# LTC6803.net
KiCad netlist of a schematic drawn in Altium Designer
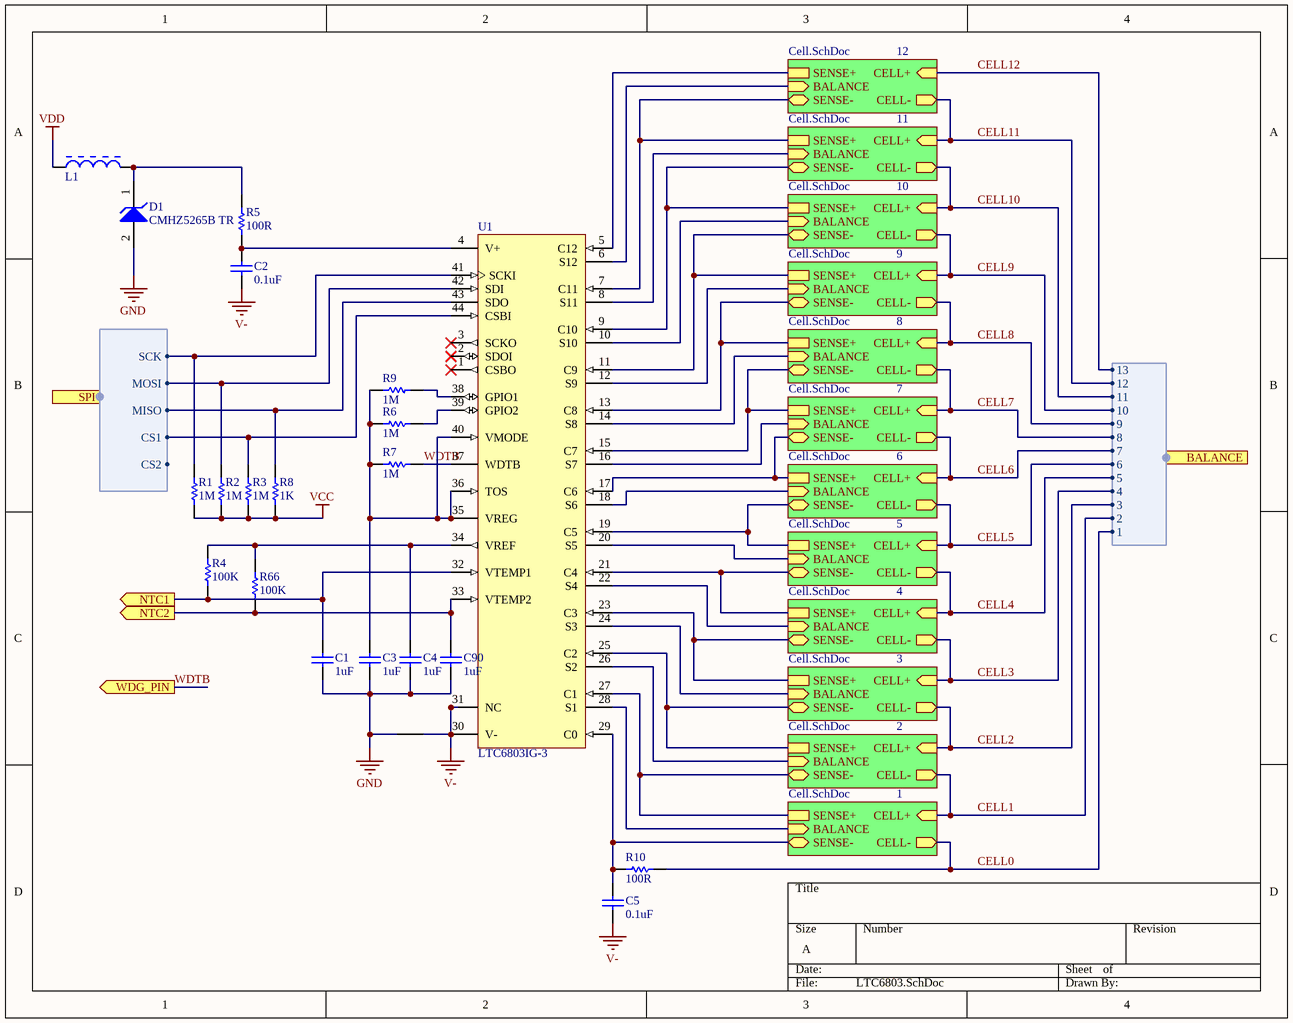
[diagram p0: LTC6803.SchDoc]

(export (version "E")
  (design (tool "Eeschema 10.0.6"))
  (components
    (comp (ref "*") (value "NetTie") (footprint "NetTie") (libsource (lib "Components") (part "NetTie")))
    (comp (ref "C1")
      (value "1uF")
      (footprint "C0603[1608X92]")
      (description "1uF 6.3V 10% 0603 (1608 Metric)")
      (fields (field (name "PARTNUMBER") "GRM188R60J105KA01D") (field (name "MANUFACTURER") "Murata"))
      (libsource (lib "Capacitors") (part "CAP_1uF_6.3V_0603_10%"))
    )
    (comp (ref "C2")
      (value "0.1uF")
      (footprint "C0603[1608X92]")
      (description "0.1uF 100V 10% 0603 (1608 Metric)")
      (fields (field (name "PARTNUMBER") "GRM188R72A104KA35D") (field (name "MANUFACTURER") "Murata"))
      (libsource (lib "Capacitors") (part "CAP_0.1uF_100V_0603_10%"))
    )
    (comp (ref "C3")
      (value "1uF")
      (footprint "C0603[1608X92]")
      (description "1uF 6.3V 10% 0603 (1608 Metric)")
      (fields (field (name "PARTNUMBER") "GRM188R60J105KA01D") (field (name "MANUFACTURER") "Murata"))
      (libsource (lib "Capacitors") (part "CAP_1uF_6.3V_0603_10%"))
    )
    (comp (ref "C4")
      (value "1uF")
      (footprint "C0603[1608X92]")
      (description "1uF 6.3V 10% 0603 (1608 Metric)")
      (fields (field (name "PARTNUMBER") "GRM188R60J105KA01D") (field (name "MANUFACTURER") "Murata"))
      (libsource (lib "Capacitors") (part "CAP_1uF_6.3V_0603_10%"))
    )
    (comp (ref "C5")
      (value "0.1uF")
      (footprint "C0603[1608X92]")
      (description "0.1uF 6.3V 10% 0603 (1608 Metric)")
      (fields (field (name "PARTNUMBER") "GRM188R70J104KA01D") (field (name "MANUFACTURER") "Murata"))
      (libsource (lib "Capacitors") (part "CAP_0.1uF_6.3V_0603_10%"))
    )
    (comp (ref "C90")
      (value "1uF")
      (footprint "C0603[1608X92]")
      (description "1uF 6.3V 10% 0603 (1608 Metric)")
      (fields (field (name "PARTNUMBER") "GRM188R60J105KA01D") (field (name "MANUFACTURER") "Murata"))
      (libsource (lib "Capacitors") (part "CAP_1uF_6.3V_0603_10%"))
    )
    (comp (ref "D1")
      (value "CMHZ5265B TR")
      (footprint "SOD-123")
      (description "Zener Diodes 500mW Zener Diode 185mA 58.9V to 2V")
      (fields (field (name "PARTNUMBER") "CMHZ5265B") (field (name "MANUFACTURER") "Central Semiconductor"))
      (libsource (lib "Diodes") (part "CMHZ5265B"))
    )
    (comp (ref "L1")
      (value "MURA-FB-2")
      (footprint "MURA-BLM31-B60-CHIP-2_V3")
      (description "EMI Filter Beads, Chips & Arrays 1206 33 OHM")
      (fields (field (name "PARTNUMBER") "BLM31PG330SN1L") (field (name "MANUFACTURER") "Murata"))
      (libsource (lib "Components") (part "MURA-FB-2"))
    )
    (comp (ref "R1")
      (value "1M")
      (footprint "R0603[1608]")
      (description "1M 0.25W 5% 0603 (1005 Metric)")
      (fields (field (name "MANUFACTURER") "Panasonic") (field (name "PARTNUMBER") "ERJ-PA3J105V"))
      (libsource (lib "Resistors") (part "RES_1M_0603_5%"))
    )
    (comp (ref "R2")
      (value "1M")
      (footprint "R0603[1608]")
      (description "1M 0.25W 5% 0603 (1005 Metric)")
      (fields (field (name "MANUFACTURER") "Panasonic") (field (name "PARTNUMBER") "ERJ-PA3J105V"))
      (libsource (lib "Resistors") (part "RES_1M_0603_5%"))
    )
    (comp (ref "R3")
      (value "1M")
      (footprint "R0603[1608]")
      (description "1M 0.25W 5% 0603 (1005 Metric)")
      (fields (field (name "MANUFACTURER") "Panasonic") (field (name "PARTNUMBER") "ERJ-PA3J105V"))
      (libsource (lib "Resistors") (part "RES_1M_0603_5%"))
    )
    (comp (ref "R4")
      (value "100K")
      (footprint "R0603[1608]")
      (description "100K 0.25W 1% 0603 (1005 Metric)")
      (fields (field (name "MANUFACTURER") "Vishay / Dale") (field (name "PARTNUMBER") "CRCW0603100KFKEAHP"))
      (libsource (lib "Resistors") (part "RES_100K_0603_1%"))
    )
    (comp (ref "R5")
      (value "100R")
      (footprint "R0603[1608]")
      (description "100R 0.25W 1% 0603 (1005 Metric)")
      (fields (field (name "MANUFACTURER") "Vishay / Dale") (field (name "PARTNUMBER") "CRCW0603100RFKEAHP"))
      (libsource (lib "Resistors") (part "RES_100R_0603_1%"))
    )
    (comp (ref "R6")
      (value "1M")
      (footprint "R0603[1608]")
      (description "1M 0.25W 5% 0603 (1005 Metric)")
      (fields (field (name "MANUFACTURER") "Panasonic") (field (name "PARTNUMBER") "ERJ-PA3J105V"))
      (libsource (lib "Resistors") (part "RES_1M_0603_5%"))
    )
    (comp (ref "R7")
      (value "1M")
      (footprint "R0603[1608]")
      (description "1M 0.25W 5% 0603 (1005 Metric)")
      (fields (field (name "MANUFACTURER") "Panasonic") (field (name "PARTNUMBER") "ERJ-PA3J105V"))
      (libsource (lib "Resistors") (part "RES_1M_0603_5%"))
    )
    (comp (ref "R8")
      (value "1K")
      (footprint "R0603[1608]")
      (description "1K 0.25W 1% 0603 (1005 Metric)")
      (fields (field (name "MANUFACTURER") "Vishay / Dale") (field (name "PARTNUMBER") "CRCW06031K00FKEAHP"))
      (libsource (lib "Resistors") (part "RES_1K_0603_1%"))
    )
    (comp (ref "R9")
      (value "1M")
      (footprint "R0603[1608]")
      (description "1M 0.25W 5% 0603 (1005 Metric)")
      (fields (field (name "MANUFACTURER") "Panasonic") (field (name "PARTNUMBER") "ERJ-PA3J105V"))
      (libsource (lib "Resistors") (part "RES_1M_0603_5%"))
    )
    (comp (ref "R10")
      (value "100R")
      (footprint "R0603[1608]")
      (description "100R 0.25W 1% 0603 (1005 Metric)")
      (fields (field (name "MANUFACTURER") "Vishay / Dale") (field (name "PARTNUMBER") "CRCW0603100RFKEAHP"))
      (libsource (lib "Resistors") (part "RES_100R_0603_1%"))
    )
    (comp (ref "R66")
      (value "100K")
      (footprint "R0603[1608]")
      (description "100K 0.25W 1% 0603 (1005 Metric)")
      (fields (field (name "MANUFACTURER") "Vishay / Dale") (field (name "PARTNUMBER") "CRCW0603100KFKEAHP"))
      (libsource (lib "Resistors") (part "RES_100K_0603_1%"))
    )
    (comp (ref "U1")
      (value "LTC6803IG-3")
      (footprint "TSSOP-44")
      (fields (field (name "PARTNUMBER") "LTC6803IG-3#PBF") (field (name "MANUFACTURER") "Linear Technology"))
      (libsource (lib "ICs") (part "LTC6803IG-3"))
    )
  )
  (nets
    (net (code "3") (name "/BALANCE") (class "Default")
      (node (ref "U1") (pin "18") (pinfunction "S6_18") (pintype "tri_state"))
    )
    (net (code "4") (name "/BALANCE_1") (class "Default")
      (node (ref "U1") (pin "6") (pinfunction "S12_6") (pintype "tri_state"))
    )
    (net (code "5") (name "/BALANCE_2") (class "Default")
      (node (ref "U1") (pin "8") (pinfunction "S11_8") (pintype "tri_state"))
    )
    (net (code "6") (name "/BALANCE_3") (class "Default")
      (node (ref "U1") (pin "10") (pinfunction "S10_10") (pintype "tri_state"))
    )
    (net (code "7") (name "/BALANCE_4") (class "Default")
      (node (ref "U1") (pin "12") (pinfunction "S9_12") (pintype "tri_state"))
    )
    (net (code "8") (name "/BALANCE_5") (class "Default")
      (node (ref "U1") (pin "28") (pinfunction "S1_28") (pintype "tri_state"))
    )
    (net (code "9") (name "/BALANCE_6") (class "Default")
      (node (ref "U1") (pin "26") (pinfunction "S2_26") (pintype "tri_state"))
    )
    (net (code "10") (name "/BALANCE_7") (class "Default")
      (node (ref "U1") (pin "24") (pinfunction "S3_24") (pintype "tri_state"))
    )
    (net (code "11") (name "/BALANCE_8") (class "Default")
      (node (ref "U1") (pin "22") (pinfunction "S4_22") (pintype "tri_state"))
    )
    (net (code "12") (name "/BALANCE_9") (class "Default")
      (node (ref "U1") (pin "16") (pinfunction "S7_16") (pintype "tri_state"))
    )
    (net (code "13") (name "/BALANCE_10") (class "Default")
      (node (ref "U1") (pin "14") (pinfunction "S8_14") (pintype "tri_state"))
    )
    (net (code "14") (name "/BALANCE_11") (class "Default")
      (node (ref "U1") (pin "20") (pinfunction "S5_20") (pintype "tri_state"))
    )
    (net (code "15") (name "/CELL0") (class "Default")
      (node (ref "R10") (pin "1") (pinfunction "1_1") (pintype "passive"))
    )
    (net (code "28") (name "/NTC1") (class "Default")
      (node (ref "C1") (pin "2") (pinfunction "2_2") (pintype "passive"))
      (node (ref "R4") (pin "1") (pinfunction "1_1") (pintype "passive"))
      (node (ref "U1") (pin "32") (pinfunction "VTEMP1_32") (pintype "input"))
    )
    (net (code "29") (name "/NTC2") (class "Default")
      (node (ref "C90") (pin "2") (pinfunction "2_2") (pintype "passive"))
      (node (ref "R66") (pin "1") (pinfunction "1_1") (pintype "passive"))
      (node (ref "U1") (pin "33") (pinfunction "VTEMP2_33") (pintype "input"))
    )
    (net (code "30") (name "/SENSE+") (class "Default")
      (node (ref "U1") (pin "19") (pinfunction "C5_19") (pintype "input"))
    )
    (net (code "31") (name "/SENSE+_1") (class "Default")
      (node (ref "U1") (pin "5") (pinfunction "C12_5") (pintype "input"))
    )
    (net (code "32") (name "/SENSE+_2") (class "Default")
      (node (ref "U1") (pin "7") (pinfunction "C11_7") (pintype "input"))
    )
    (net (code "33") (name "/SENSE+_3") (class "Default")
      (node (ref "U1") (pin "9") (pinfunction "C10_9") (pintype "input"))
    )
    (net (code "34") (name "/SENSE+_4") (class "Default")
      (node (ref "U1") (pin "11") (pinfunction "C9_11") (pintype "input"))
    )
    (net (code "35") (name "/SENSE+_5") (class "Default")
      (node (ref "U1") (pin "13") (pinfunction "C8_13") (pintype "input"))
    )
    (net (code "36") (name "/SENSE+_6") (class "Default")
      (node (ref "U1") (pin "27") (pinfunction "C1_27") (pintype "input"))
    )
    (net (code "37") (name "/SENSE+_7") (class "Default")
      (node (ref "U1") (pin "25") (pinfunction "C2_25") (pintype "input"))
    )
    (net (code "38") (name "/SENSE+_8") (class "Default")
      (node (ref "U1") (pin "23") (pinfunction "C3_23") (pintype "input"))
    )
    (net (code "39") (name "/SENSE+_9") (class "Default")
      (node (ref "U1") (pin "15") (pinfunction "C7_15") (pintype "input"))
    )
    (net (code "40") (name "/SENSE+_10") (class "Default")
      (node (ref "U1") (pin "17") (pinfunction "C6_17") (pintype "input"))
    )
    (net (code "41") (name "/SENSE+_11") (class "Default")
      (node (ref "U1") (pin "21") (pinfunction "C4_21") (pintype "input"))
    )
    (net (code "42") (name "/SENSE-") (class "Default")
      (node (ref "C5") (pin "2") (pinfunction "2_2") (pintype "passive"))
      (node (ref "R10") (pin "2") (pinfunction "2_2") (pintype "passive"))
      (node (ref "U1") (pin "29") (pinfunction "C0_29") (pintype "input"))
    )
    (net (code "43") (name "/WDTB") (class "Default")
      (node (ref "R7") (pin "1") (pinfunction "1_1") (pintype "passive"))
      (node (ref "U1") (pin "37") (pinfunction "WDTB_37") (pintype "open_collector"))
    )
    (net (code "46") (name "GND") (class "Default")
      (node (ref "*") (pin "1") (pinfunction "1_1") (pintype "passive"))
      (node (ref "C1") (pin "1") (pinfunction "1_1") (pintype "passive"))
      (node (ref "C3") (pin "1") (pinfunction "1_1") (pintype "passive"))
      (node (ref "C4") (pin "1") (pinfunction "1_1") (pintype "passive"))
      (node (ref "C90") (pin "1") (pinfunction "1_1") (pintype "passive"))
      (node (ref "D1") (pin "2") (pinfunction "A_2") (pintype "passive"))
    )
    (net (code "47") (name "Net-(D1-K)") (class "Default")
      (node (ref "D1") (pin "1") (pinfunction "K_1") (pintype "passive"))
      (node (ref "L1") (pin "2") (pinfunction "2_2") (pintype "passive"))
      (node (ref "R5") (pin "2") (pinfunction "2_2") (pintype "passive"))
    )
    (net (code "48") (name "Net-(U1-CSBI)") (class "Default")
      (node (ref "R3") (pin "2") (pinfunction "2_2") (pintype "passive"))
      (node (ref "U1") (pin "44") (pinfunction "CSBI_44") (pintype "input"))
    )
    (net (code "49") (name "Net-(U1-GPIO1)") (class "Default")
      (node (ref "R9") (pin "1") (pinfunction "1_1") (pintype "passive"))
      (node (ref "U1") (pin "38") (pinfunction "GPIO1_38") (pintype "bidirectional"))
    )
    (net (code "50") (name "Net-(U1-GPIO2)") (class "Default")
      (node (ref "R6") (pin "1") (pinfunction "1_1") (pintype "passive"))
      (node (ref "U1") (pin "39") (pinfunction "GPIO2_39") (pintype "bidirectional"))
    )
    (net (code "51") (name "Net-(U1-SCKI)") (class "Default")
      (node (ref "R1") (pin "2") (pinfunction "2_2") (pintype "passive"))
      (node (ref "U1") (pin "41") (pinfunction "SCKI_41") (pintype "input"))
    )
    (net (code "52") (name "Net-(U1-SDI)") (class "Default")
      (node (ref "R2") (pin "2") (pinfunction "2_2") (pintype "passive"))
      (node (ref "U1") (pin "42") (pinfunction "SDI_42") (pintype "input"))
    )
    (net (code "53") (name "Net-(U1-SDO)") (class "Default")
      (node (ref "R8") (pin "2") (pinfunction "2_2") (pintype "passive"))
      (node (ref "U1") (pin "43") (pinfunction "SDO_43") (pintype "open_collector"))
    )
    (net (code "54") (name "Net-(U1-TOS)") (class "Default")
      (node (ref "C3") (pin "2") (pinfunction "2_2") (pintype "passive"))
      (node (ref "R6") (pin "2") (pinfunction "2_2") (pintype "passive"))
      (node (ref "R7") (pin "2") (pinfunction "2_2") (pintype "passive"))
      (node (ref "R9") (pin "2") (pinfunction "2_2") (pintype "passive"))
      (node (ref "U1") (pin "35") (pinfunction "VREG_35") (pintype "power_in"))
      (node (ref "U1") (pin "36") (pinfunction "TOS_36") (pintype "input"))
      (node (ref "U1") (pin "40") (pinfunction "VMODE_40") (pintype "input"))
    )
    (net (code "55") (name "Net-(U1-V+)") (class "Default")
      (node (ref "C2") (pin "2") (pinfunction "2_2") (pintype "passive"))
      (node (ref "R5") (pin "1") (pinfunction "1_1") (pintype "passive"))
      (node (ref "U1") (pin "4") (pinfunction "V+_4") (pintype "power_in"))
    )
    (net (code "56") (name "Net-(U1-VREF)") (class "Default")
      (node (ref "C4") (pin "2") (pinfunction "2_2") (pintype "passive"))
      (node (ref "R4") (pin "2") (pinfunction "2_2") (pintype "passive"))
      (node (ref "R66") (pin "2") (pinfunction "2_2") (pintype "passive"))
      (node (ref "U1") (pin "34") (pinfunction "VREF_34") (pintype "output"))
    )
    (net (code "57") (name "V-") (class "Default")
      (node (ref "*") (pin "2") (pinfunction "2_2") (pintype "passive"))
      (node (ref "C2") (pin "1") (pinfunction "1_1") (pintype "passive"))
      (node (ref "C5") (pin "1") (pinfunction "1_1") (pintype "passive"))
      (node (ref "U1") (pin "30") (pinfunction "V-_30") (pintype "power_in"))
      (node (ref "U1") (pin "31") (pinfunction "NC_31") (pintype "passive"))
    )
    (net (code "58") (name "VCC") (class "Default")
      (node (ref "R1") (pin "1") (pinfunction "1_1") (pintype "passive"))
      (node (ref "R2") (pin "1") (pinfunction "1_1") (pintype "passive"))
      (node (ref "R3") (pin "1") (pinfunction "1_1") (pintype "passive"))
      (node (ref "R8") (pin "1") (pinfunction "1_1") (pintype "passive"))
    )
    (net (code "59") (name "VDD") (class "Default")
      (node (ref "L1") (pin "1") (pinfunction "1_1") (pintype "passive"))
    )
    (net (code "60") (name "unconnected-(U1-CSBO-Pad1)") (class "Default")
      (node (ref "U1") (pin "1") (pinfunction "CSBO_1") (pintype "output+no_connect"))
    )
    (net (code "61") (name "unconnected-(U1-SCKO-Pad3)") (class "Default")
      (node (ref "U1") (pin "3") (pinfunction "SCKO_3") (pintype "output+no_connect"))
    )
    (net (code "62") (name "unconnected-(U1-SDOI-Pad2)") (class "Default")
      (node (ref "U1") (pin "2") (pinfunction "SDOI_2") (pintype "bidirectional+no_connect"))
    )
  )
)
